# Sheet1.net
KiCad netlist of a schematic drawn in Altium Designer
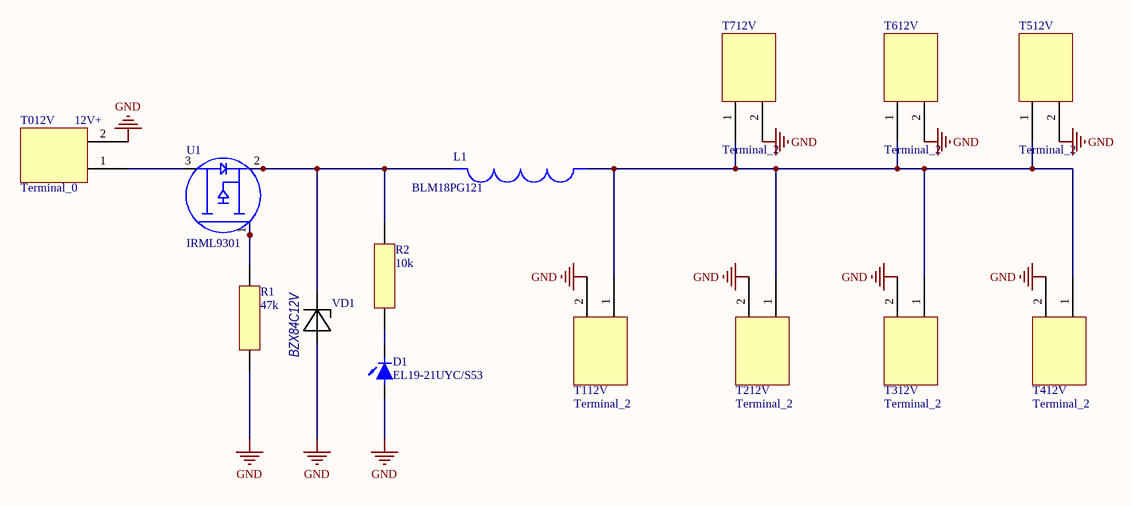
[diagram p0: Sheet1.SchDoc]

(export (version "E")
  (design (tool "Eeschema 10.0.6"))
  (components
    (comp (ref "D1")
      (value "EL19-21UYC/S53")
      (footprint "0603_LED")
      (description "Typical INFRARED GaAs LED")
      (fields (field (name "PUBLISHER") "Altium Limited"))
      (libsource (lib "my_lib") (part "LED"))
    )
    (comp (ref "L1")
      (value "BLM18PG121")
      (footprint "0603ind")
      (description "Inductor")
      (fields (field (name "MANUFACTURERPARTNUMBER") "BLM18PG121TN1D"))
      (libsource (lib "my_lib") (part "L"))
    )
    (comp (ref "R1")
      (value "47k")
      (footprint "0603_RES")
      (description "RC0603FR-0747kL")
      (libsource (lib "my_lib") (part "R"))
    )
    (comp (ref "R2")
      (value "10k")
      (footprint "0603_RES")
      (description "RC0603FR-0747kL")
      (libsource (lib "") (part "R_1"))
    )
    (comp (ref "T012V")
      (value "Terminal_0")
      (footprint "TERMINAL_2_3.5")
      (libsource (lib "") (part "Terminal_2_1"))
    )
    (comp (ref "T112V")
      (value "Terminal_2")
      (footprint "TERMINAL_2_3.5")
      (libsource (lib "my_2") (part "Terminal_2"))
    )
    (comp (ref "T212V")
      (value "Terminal_2")
      (footprint "TERMINAL_2_3.5")
      (libsource (lib "my_2") (part "Terminal_2"))
    )
    (comp (ref "T312V")
      (value "Terminal_2")
      (footprint "TERMINAL_2_3.5")
      (libsource (lib "my_2") (part "Terminal_2"))
    )
    (comp (ref "T412V")
      (value "Terminal_2")
      (footprint "TERMINAL_2_3.5")
      (libsource (lib "my_2") (part "Terminal_2"))
    )
    (comp (ref "T512V")
      (value "Terminal_2")
      (footprint "TERMINAL_2_3.5")
      (libsource (lib "") (part "Terminal_2_2"))
    )
    (comp (ref "T612V")
      (value "Terminal_2")
      (footprint "TERMINAL_2_3.5")
      (libsource (lib "") (part "Terminal_2_2"))
    )
    (comp (ref "T712V")
      (value "Terminal_2")
      (footprint "TERMINAL_2_3.5")
      (libsource (lib "") (part "Terminal_2_2"))
    )
    (comp (ref "U1")
      (value "IRML9301")
      (footprint "MICRO3_NORM")
      (description "IRLML9301TRPBF")
      (libsource (lib "my_lib") (part "IRML5203"))
    )
    (comp (ref "VD1")
      (value "BZX84C12V")
      (footprint "SOT23")
      (description "DIODE ZENER 12V 350MW SOT23-3")
      (fields (field (name "PART NUMBER") "BZX84C12") (field (name "MANUFACTURER") "Fairchild Semiconductor"))
      (libsource (lib "my_lib") (part "DIODE_STAB_BZX84_GOST"))
    )
  )
  (nets
    (net (code "1") (name "GND") (class "Default")
      (node (ref "D1") (pin "1") (pinfunction "A_1") (pintype "passive"))
      (node (ref "R1") (pin "2") (pinfunction "V-_2") (pintype "passive"))
      (node (ref "T012V") (pin "2") (pinfunction "2_2") (pintype "passive"))
      (node (ref "T112V") (pin "2") (pinfunction "2_2") (pintype "passive"))
      (node (ref "T212V") (pin "2") (pinfunction "2_2") (pintype "passive"))
      (node (ref "T312V") (pin "2") (pinfunction "2_2") (pintype "passive"))
      (node (ref "T412V") (pin "2") (pinfunction "2_2") (pintype "passive"))
      (node (ref "T512V") (pin "2") (pinfunction "2_2") (pintype "passive"))
      (node (ref "T612V") (pin "2") (pinfunction "2_2") (pintype "passive"))
      (node (ref "T712V") (pin "2") (pinfunction "2_2") (pintype "passive"))
      (node (ref "VD1") (pin "1") (pintype "passive"))
    )
    (net (code "2") (name "Net-(D1-K)") (class "Default")
      (node (ref "D1") (pin "2") (pinfunction "K_2") (pintype "passive"))
      (node (ref "R2") (pin "1") (pinfunction "V+_1") (pintype "passive"))
    )
    (net (code "3") (name "Net-(L1-Pad1)") (class "Default")
      (node (ref "L1") (pin "1") (pinfunction "1_1") (pintype "passive"))
      (node (ref "T112V") (pin "1") (pinfunction "1_1") (pintype "passive"))
      (node (ref "T212V") (pin "1") (pinfunction "1_1") (pintype "passive"))
      (node (ref "T312V") (pin "1") (pinfunction "1_1") (pintype "passive"))
      (node (ref "T412V") (pin "1") (pinfunction "1_1") (pintype "passive"))
      (node (ref "T512V") (pin "1") (pinfunction "1_1") (pintype "passive"))
      (node (ref "T612V") (pin "1") (pinfunction "1_1") (pintype "passive"))
      (node (ref "T712V") (pin "1") (pinfunction "1_1") (pintype "passive"))
    )
    (net (code "4") (name "Net-(R1-V+)") (class "Default")
      (node (ref "R1") (pin "1") (pinfunction "V+_1") (pintype "passive"))
      (node (ref "U1") (pin "1") (pinfunction "1_1") (pintype "passive"))
    )
    (net (code "5") (name "Net-(R2-V-)") (class "Default")
      (node (ref "L1") (pin "2") (pinfunction "2_2") (pintype "passive"))
      (node (ref "R2") (pin "2") (pinfunction "V-_2") (pintype "passive"))
      (node (ref "U1") (pin "2") (pinfunction "2_2") (pintype "passive"))
      (node (ref "VD1") (pin "2") (pintype "passive"))
    )
    (net (code "6") (name "Net-(T012V-Pad1)") (class "Default")
      (node (ref "T012V") (pin "1") (pinfunction "1_1") (pintype "passive"))
      (node (ref "U1") (pin "3") (pinfunction "3_3") (pintype "passive"))
    )
  )
)
